# EtherWiz_Sockets.net
KiCad netlist of a schematic drawn in Altium Designer
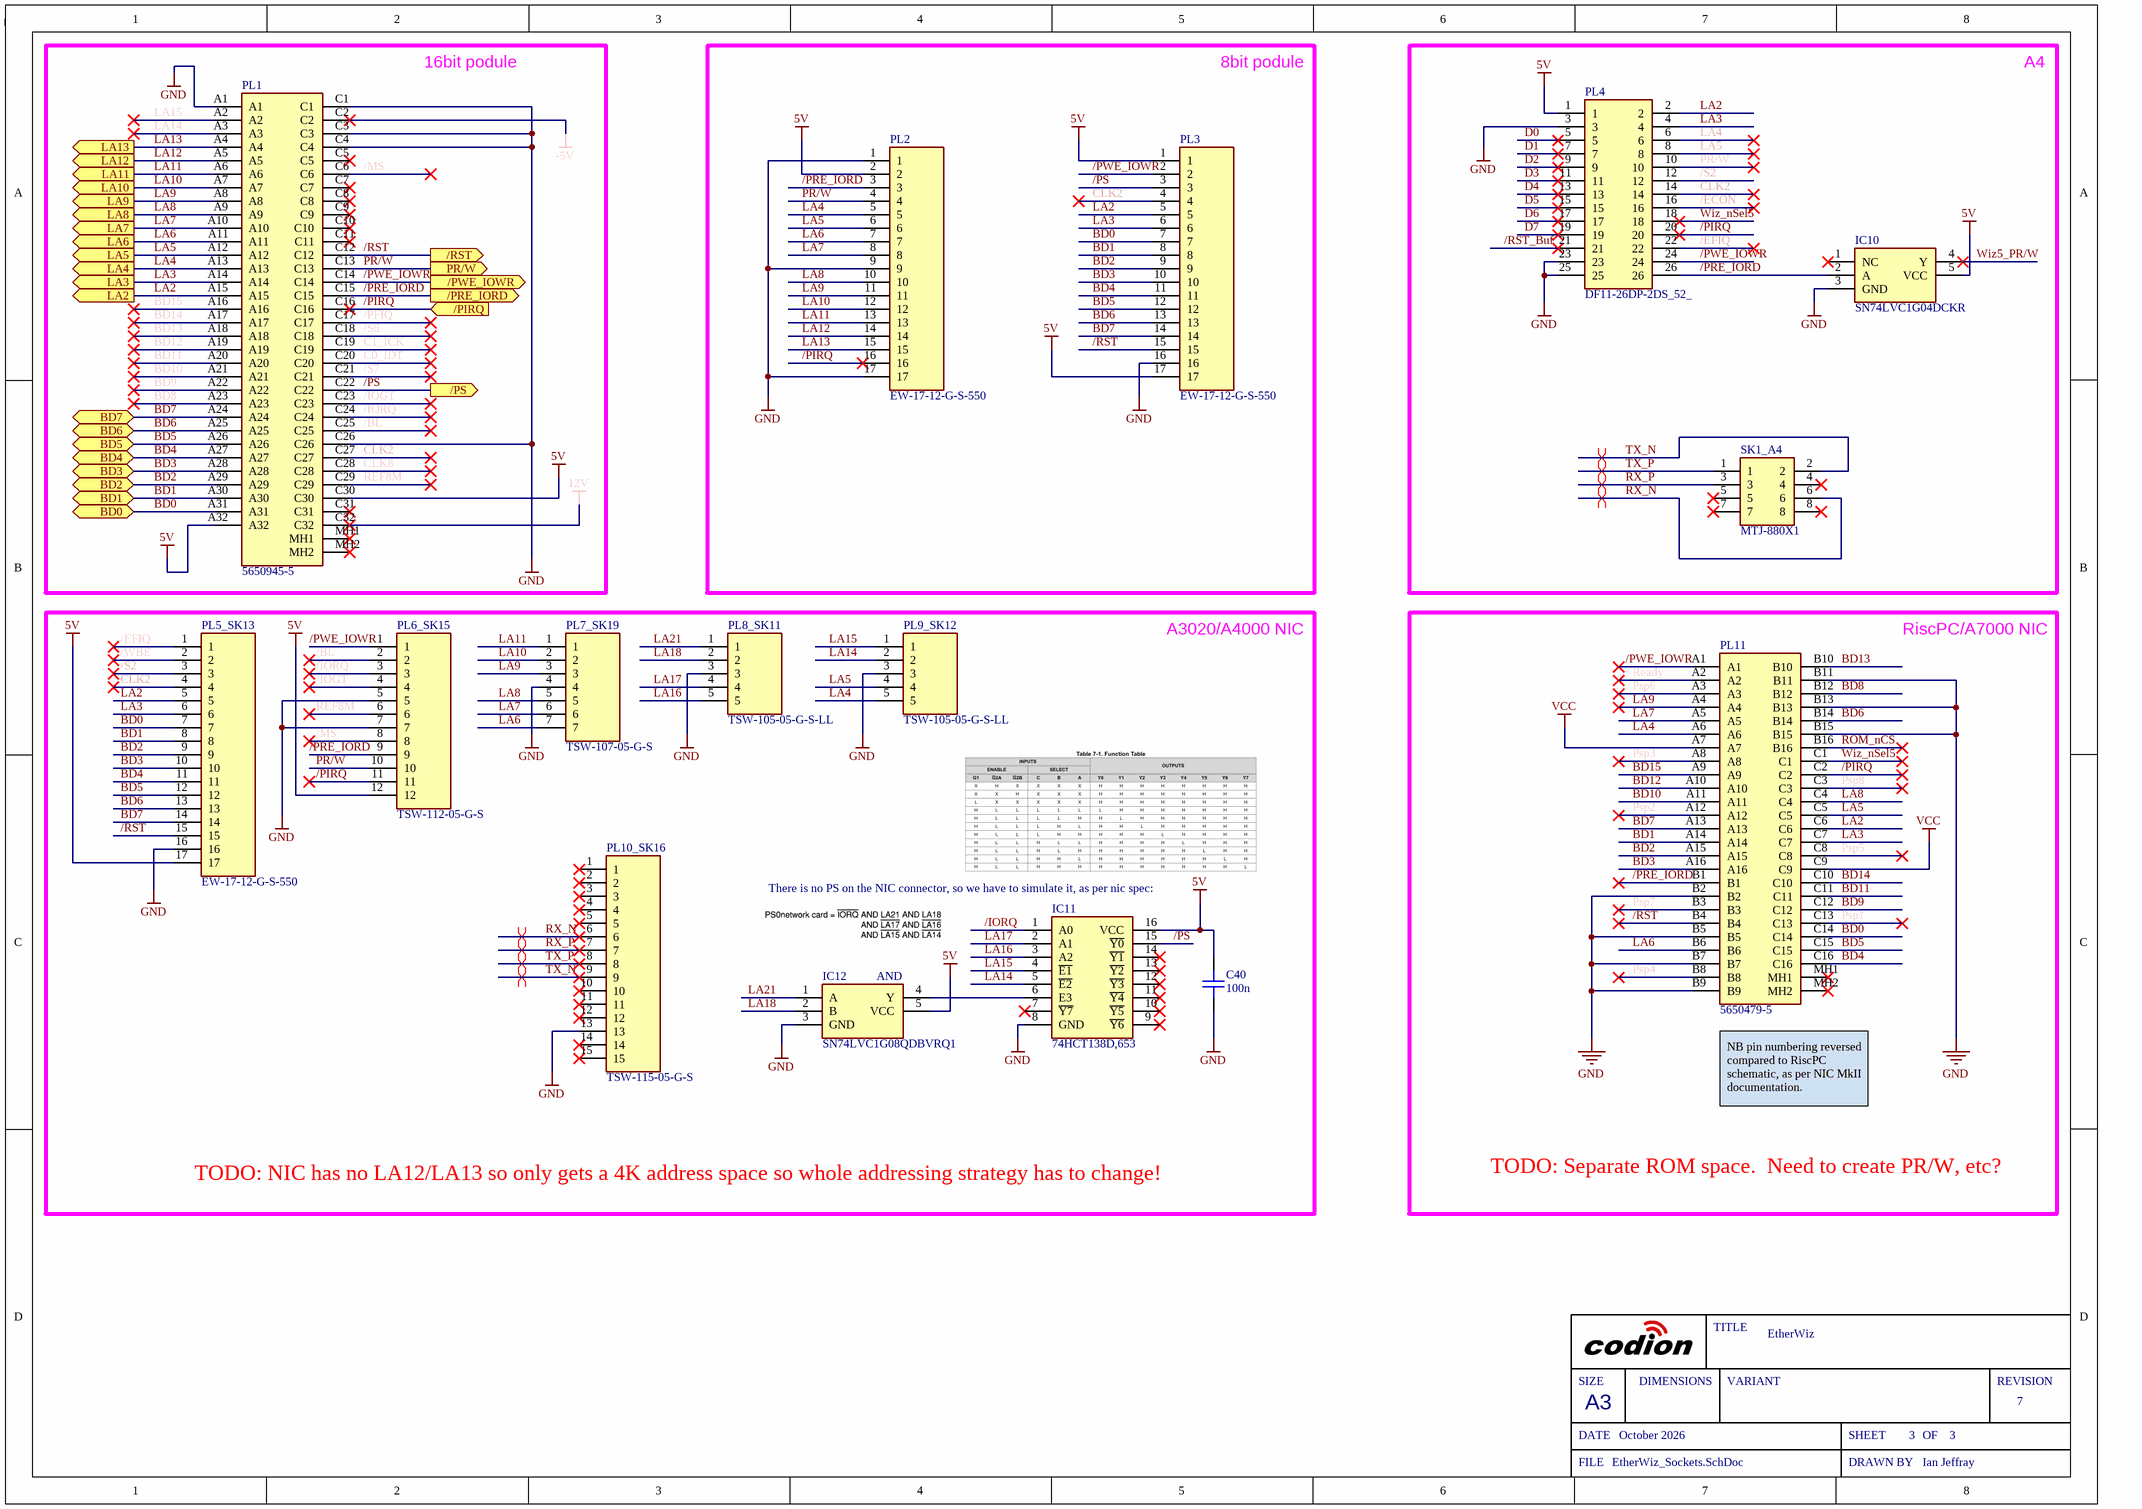
[diagram p0: EtherWiz_Sockets.SchDoc]

(export (version "E")
  (design (tool "Eeschema 10.0.6"))
  (components
    (comp (ref "C40")
      (value "100n")
      (footprint "CAPC1608L")
      (description "CAP 100nF, 0603, 50V, X7R, 10%")
      (fields
        (field (name "DISTRIBUTOR1 PART NO") "CL10B104KB8NNNC")
        (field (name "DISTRIBUTOR2 PART NO") "311-1344-2-ND")
      )
      (libsource (lib "MCP1002_RevC") (part "CAP_100n_0603_50V_0"))
    )
    (comp (ref "IC10")
      (value "SN74LVC1G04DCKR")
      (footprint "SamacSys:SOT65P210X110-5N")
      (description "Integrated Circuit")
      (fields (field (name "MOUSER PART NUMBER") "595-SN74LVC1G04DCKR"))
      (libsource (lib "*") (part "SN74LVC1G04DCKR"))
    )
    (comp (ref "IC11")
      (value "74HCT138D,653")
      (footprint "SamacSys:SOIC127P600X175-16N")
      (description "Integrated Circuit")
      (fields (field (name "MOUSER PART NUMBER") "771-74HCT138D-T"))
      (libsource (lib "*") (part "74HCT138D,653"))
    )
    (comp (ref "IC12")
      (value "SN74LVC1G08QDBVRQ1")
      (footprint "SamacSys:SOT95P280X145-5N")
      (description "Integrated Circuit")
      (fields (field (name "MOUSER PART NUMBER") "595-SN74LVC1G08QDBQ1"))
      (libsource (lib "*") (part "SN74LVC1G08QDBVRQ1"))
    )
    (comp (ref "PL1")
      (value "5650945-5")
      (footprint "SamacSys:56509455")
      (description "Connector")
      (fields (field (name "MOUSER PART NUMBER") "571-5650945-5"))
      (libsource (lib "Acorn") (part "5650945-5"))
    )
    (comp (ref "PL2")
      (value "EW-17-12-G-S-550")
      (footprint "SamacSys:TSW-117-XX-YY-S")
      (description "Connector")
      (fields (field (name "MANUFACTURER_PART_NUMBER") "TSW-117-05-G-S"))
      (libsource (lib "*") (part "TSW-117-05-G-S"))
    )
    (comp (ref "PL3")
      (value "EW-17-12-G-S-550")
      (footprint "SamacSys:TSW-117-XX-YY-S")
      (description "Connector")
      (fields (field (name "MANUFACTURER_PART_NUMBER") "TSW-117-05-G-S"))
      (libsource (lib "*") (part "TSW-117-05-G-S"))
    )
    (comp (ref "PL4")
      (value "DF11-26DP-2DS_52_")
      (footprint "SamacSys:SHDRRA26W50P200_2X13_2800X1000X500P")
      (description "Connector")
      (fields
        (field (name "MANUFACTURER_PART_NUMBER") "DF11-26DP-2DS(52)")
        (field (name "MOUSER PART NUMBER") "798-DF11-26DP-2DS52")
      )
      (libsource (lib "*") (part "DF11-26DP-2DS_52_"))
    )
    (comp (ref "PL5_SK13")
      (value "EW-17-12-G-S-550")
      (footprint "SamacSys:TSW-117-XX-YY-S")
      (description "Connector")
      (fields (field (name "MANUFACTURER_PART_NUMBER") "TSW-117-05-G-S"))
      (libsource (lib "*") (part "TSW-117-05-G-S"))
    )
    (comp (ref "PL6_SK15")
      (value "TSW-112-05-G-S")
      (footprint "SamacSys:TSW-112-XX-YY-S")
      (description "Connector")
      (libsource (lib "*") (part "TSW-112-05-G-S"))
    )
    (comp (ref "PL7_SK19")
      (value "TSW-107-05-G-S")
      (footprint "SamacSys:TSW-107-XX-YY-S")
      (description "Connector")
      (libsource (lib "*") (part "TSW-107-05-G-S"))
    )
    (comp (ref "PL8_SK11")
      (value "TSW-105-05-G-S-LL")
      (footprint "SamacSys:HDRV5W64P0X254_1X5_1270X254X521P")
      (description "Connector")
      (libsource (lib "*") (part "TSW-105-05-G-S-LL"))
    )
    (comp (ref "PL9_SK12")
      (value "TSW-105-05-G-S-LL")
      (footprint "SamacSys:HDRV5W64P0X254_1X5_1270X254X521P")
      (description "Connector")
      (libsource (lib "*") (part "TSW-105-05-G-S-LL"))
    )
    (comp (ref "PL10_SK16")
      (value "TSW-115-05-G-S")
      (footprint "SamacSys:TSW-115-XX-YY-S")
      (description "Connector")
      (libsource (lib "*") (part "TSW-115-05-G-S"))
    )
    (comp (ref "PL11")
      (value "5650479-5")
      (footprint "SamacSys:56504795")
      (description "Connector")
      (fields (field (name "MOUSER PART NUMBER") "571-5650479-5"))
      (libsource (lib "*") (part "5650479-5"))
    )
    (comp (ref "SK1_A4")
      (value "MTJ-880X1")
      (footprint "SamacSys:MTJ880X1")
      (description "Connector")
      (fields (field (name "MOUSER PART NUMBER") "737-MTJ-880X1"))
      (libsource (lib "*") (part "MTJ-880X1"))
    )
  )
  (nets
    (net (code "1") (name "-5V") (class "Default")
      (node (ref "PL1") (pin "C2") (pinfunction "C2_C2") (pintype "passive"))
    )
    (net (code "2") (name "/BD0") (class "Default")
      (node (ref "PL1") (pin "A31") (pinfunction "A31_A31") (pintype "passive"))
      (node (ref "PL11") (pin "C14") (pinfunction "C14_C14") (pintype "passive"))
      (node (ref "PL3") (pin "7") (pinfunction "7_7") (pintype "passive"))
      (node (ref "PL5_SK13") (pin "7") (pinfunction "7_7") (pintype "passive"))
    )
    (net (code "3") (name "/BD1") (class "Default")
      (node (ref "PL1") (pin "A30") (pinfunction "A30_A30") (pintype "passive"))
      (node (ref "PL11") (pin "A14") (pinfunction "A14_A14") (pintype "passive"))
      (node (ref "PL3") (pin "8") (pinfunction "8_8") (pintype "passive"))
      (node (ref "PL5_SK13") (pin "8") (pinfunction "8_8") (pintype "passive"))
    )
    (net (code "4") (name "/BD2") (class "Default")
      (node (ref "PL1") (pin "A29") (pinfunction "A29_A29") (pintype "passive"))
      (node (ref "PL11") (pin "A15") (pinfunction "A15_A15") (pintype "passive"))
      (node (ref "PL3") (pin "9") (pinfunction "9_9") (pintype "passive"))
      (node (ref "PL5_SK13") (pin "9") (pinfunction "9_9") (pintype "passive"))
    )
    (net (code "5") (name "/BD3") (class "Default")
      (node (ref "PL1") (pin "A28") (pinfunction "A28_A28") (pintype "passive"))
      (node (ref "PL11") (pin "A16") (pinfunction "A16_A16") (pintype "passive"))
      (node (ref "PL3") (pin "10") (pinfunction "10_10") (pintype "passive"))
      (node (ref "PL5_SK13") (pin "10") (pinfunction "10_10") (pintype "passive"))
    )
    (net (code "6") (name "/BD4") (class "Default")
      (node (ref "PL1") (pin "A27") (pinfunction "A27_A27") (pintype "passive"))
      (node (ref "PL11") (pin "C16") (pinfunction "C16_C16") (pintype "passive"))
      (node (ref "PL3") (pin "11") (pinfunction "11_11") (pintype "passive"))
      (node (ref "PL5_SK13") (pin "11") (pinfunction "11_11") (pintype "passive"))
    )
    (net (code "7") (name "/BD5") (class "Default")
      (node (ref "PL1") (pin "A26") (pinfunction "A26_A26") (pintype "passive"))
      (node (ref "PL11") (pin "C15") (pinfunction "C15_C15") (pintype "passive"))
      (node (ref "PL3") (pin "12") (pinfunction "12_12") (pintype "passive"))
      (node (ref "PL5_SK13") (pin "12") (pinfunction "12_12") (pintype "passive"))
    )
    (net (code "8") (name "/BD6") (class "Default")
      (node (ref "PL1") (pin "A25") (pinfunction "A25_A25") (pintype "passive"))
      (node (ref "PL11") (pin "B14") (pinfunction "B14_B14") (pintype "passive"))
      (node (ref "PL3") (pin "13") (pinfunction "13_13") (pintype "passive"))
      (node (ref "PL5_SK13") (pin "13") (pinfunction "13_13") (pintype "passive"))
    )
    (net (code "9") (name "/BD7") (class "Default")
      (node (ref "PL1") (pin "A24") (pinfunction "A24_A24") (pintype "passive"))
      (node (ref "PL11") (pin "A13") (pinfunction "A13_A13") (pintype "passive"))
      (node (ref "PL3") (pin "14") (pinfunction "14_14") (pintype "passive"))
      (node (ref "PL5_SK13") (pin "14") (pinfunction "14_14") (pintype "passive"))
    )
    (net (code "10") (name "/BD8") (class "Default")
      (node (ref "PL1") (pin "A23") (pinfunction "A23_A23") (pintype "passive"))
      (node (ref "PL11") (pin "B12") (pinfunction "B12_B12") (pintype "passive"))
    )
    (net (code "11") (name "/BD9") (class "Default")
      (node (ref "PL1") (pin "A22") (pinfunction "A22_A22") (pintype "passive"))
      (node (ref "PL11") (pin "C12") (pinfunction "C12_C12") (pintype "passive"))
    )
    (net (code "12") (name "/BD10") (class "Default")
      (node (ref "PL1") (pin "A21") (pinfunction "A21_A21") (pintype "passive"))
      (node (ref "PL11") (pin "A11") (pinfunction "A11_A11") (pintype "passive"))
    )
    (net (code "13") (name "/BD11") (class "Default")
      (node (ref "PL1") (pin "A20") (pinfunction "A20_A20") (pintype "passive"))
      (node (ref "PL11") (pin "C11") (pinfunction "C11_C11") (pintype "passive"))
    )
    (net (code "14") (name "/BD12") (class "Default")
      (node (ref "PL1") (pin "A19") (pinfunction "A19_A19") (pintype "passive"))
      (node (ref "PL11") (pin "A10") (pinfunction "A10_A10") (pintype "passive"))
    )
    (net (code "15") (name "/BD13") (class "Default")
      (node (ref "PL1") (pin "A18") (pinfunction "A18_A18") (pintype "passive"))
      (node (ref "PL11") (pin "B10") (pinfunction "B10_B10") (pintype "passive"))
    )
    (net (code "16") (name "/BD14") (class "Default")
      (node (ref "PL1") (pin "A17") (pinfunction "A17_A17") (pintype "passive"))
      (node (ref "PL11") (pin "C10") (pinfunction "C10_C10") (pintype "passive"))
    )
    (net (code "17") (name "/BD15") (class "Default")
      (node (ref "PL1") (pin "A16") (pinfunction "A16_A16") (pintype "passive"))
      (node (ref "PL11") (pin "A9") (pinfunction "A9_A9") (pintype "passive"))
    )
    (net (code "18") (name "/C0_IDT") (class "Default")
      (node (ref "PL1") (pin "C20") (pinfunction "C20_C20") (pintype "passive+no_connect"))
    )
    (net (code "19") (name "/C1_ICK") (class "Default")
      (node (ref "PL1") (pin "C19") (pinfunction "C19_C19") (pintype "passive+no_connect"))
    )
    (net (code "20") (name "/CLK2") (class "Default")
      (node (ref "PL1") (pin "C27") (pinfunction "C27_C27") (pintype "passive"))
      (node (ref "PL3") (pin "4") (pinfunction "4_4") (pintype "passive"))
      (node (ref "PL4") (pin "14") (pinfunction "14_14") (pintype "passive"))
      (node (ref "PL5_SK13") (pin "4") (pinfunction "4_4") (pintype "passive"))
    )
    (net (code "21") (name "/CLK8") (class "Default")
      (node (ref "PL1") (pin "C28") (pinfunction "C28_C28") (pintype "passive+no_connect"))
    )
    (net (code "22") (name "/D0") (class "Default")
      (node (ref "PL4") (pin "5") (pinfunction "5_5") (pintype "passive+no_connect"))
    )
    (net (code "23") (name "/D1") (class "Default")
      (node (ref "PL4") (pin "7") (pinfunction "7_7") (pintype "passive+no_connect"))
    )
    (net (code "24") (name "/D2") (class "Default")
      (node (ref "PL4") (pin "9") (pinfunction "9_9") (pintype "passive+no_connect"))
    )
    (net (code "25") (name "/D3") (class "Default")
      (node (ref "PL4") (pin "11") (pinfunction "11_11") (pintype "passive+no_connect"))
    )
    (net (code "26") (name "/D4") (class "Default")
      (node (ref "PL4") (pin "13") (pinfunction "13_13") (pintype "passive+no_connect"))
    )
    (net (code "27") (name "/D5") (class "Default")
      (node (ref "PL4") (pin "15") (pinfunction "15_15") (pintype "passive+no_connect"))
    )
    (net (code "28") (name "/D6") (class "Default")
      (node (ref "PL4") (pin "17") (pinfunction "17_17") (pintype "passive+no_connect"))
    )
    (net (code "29") (name "/D7") (class "Default")
      (node (ref "PL4") (pin "19") (pinfunction "19_19") (pintype "passive+no_connect"))
    )
    (net (code "30") (name "/LA2") (class "Default")
      (node (ref "PL1") (pin "A15") (pinfunction "A15_A15") (pintype "passive"))
      (node (ref "PL11") (pin "C6") (pinfunction "C6_C6") (pintype "passive"))
      (node (ref "PL3") (pin "5") (pinfunction "5_5") (pintype "passive"))
      (node (ref "PL4") (pin "2") (pinfunction "2_2") (pintype "passive"))
      (node (ref "PL5_SK13") (pin "5") (pinfunction "5_5") (pintype "passive"))
    )
    (net (code "31") (name "/LA3") (class "Default")
      (node (ref "PL1") (pin "A14") (pinfunction "A14_A14") (pintype "passive"))
      (node (ref "PL11") (pin "C7") (pinfunction "C7_C7") (pintype "passive"))
      (node (ref "PL3") (pin "6") (pinfunction "6_6") (pintype "passive"))
      (node (ref "PL4") (pin "4") (pinfunction "4_4") (pintype "passive"))
      (node (ref "PL5_SK13") (pin "6") (pinfunction "6_6") (pintype "passive"))
    )
    (net (code "32") (name "/LA4") (class "Default")
      (node (ref "PL1") (pin "A13") (pinfunction "A13_A13") (pintype "passive"))
      (node (ref "PL11") (pin "A6") (pinfunction "A6_A6") (pintype "passive"))
      (node (ref "PL2") (pin "5") (pinfunction "5_5") (pintype "passive"))
      (node (ref "PL4") (pin "6") (pinfunction "6_6") (pintype "passive"))
      (node (ref "PL9_SK12") (pin "5") (pinfunction "5_5") (pintype "passive"))
    )
    (net (code "33") (name "/LA5") (class "Default")
      (node (ref "PL1") (pin "A12") (pinfunction "A12_A12") (pintype "passive"))
      (node (ref "PL11") (pin "C5") (pinfunction "C5_C5") (pintype "passive"))
      (node (ref "PL2") (pin "6") (pinfunction "6_6") (pintype "passive"))
      (node (ref "PL4") (pin "8") (pinfunction "8_8") (pintype "passive"))
      (node (ref "PL9_SK12") (pin "4") (pinfunction "4_4") (pintype "passive"))
    )
    (net (code "34") (name "/LA6") (class "Default")
      (node (ref "PL1") (pin "A11") (pinfunction "A11_A11") (pintype "passive"))
      (node (ref "PL11") (pin "B6") (pinfunction "B6_B6") (pintype "passive"))
      (node (ref "PL2") (pin "7") (pinfunction "7_7") (pintype "passive"))
      (node (ref "PL7_SK19") (pin "7") (pinfunction "7_7") (pintype "passive"))
    )
    (net (code "35") (name "/LA7") (class "Default")
      (node (ref "PL1") (pin "A10") (pinfunction "A10_A10") (pintype "passive"))
      (node (ref "PL11") (pin "A5") (pinfunction "A5_A5") (pintype "passive"))
      (node (ref "PL2") (pin "8") (pinfunction "8_8") (pintype "passive"))
      (node (ref "PL7_SK19") (pin "6") (pinfunction "6_6") (pintype "passive"))
    )
    (net (code "36") (name "/LA8") (class "Default")
      (node (ref "PL1") (pin "A9") (pinfunction "A9_A9") (pintype "passive"))
      (node (ref "PL11") (pin "C4") (pinfunction "C4_C4") (pintype "passive"))
      (node (ref "PL2") (pin "10") (pinfunction "10_10") (pintype "passive"))
      (node (ref "PL7_SK19") (pin "5") (pinfunction "5_5") (pintype "passive"))
    )
    (net (code "37") (name "/LA9") (class "Default")
      (node (ref "PL1") (pin "A8") (pinfunction "A8_A8") (pintype "passive"))
      (node (ref "PL11") (pin "A4") (pinfunction "A4_A4") (pintype "passive"))
      (node (ref "PL2") (pin "11") (pinfunction "11_11") (pintype "passive"))
      (node (ref "PL7_SK19") (pin "3") (pinfunction "3_3") (pintype "passive"))
    )
    (net (code "38") (name "/LA10") (class "Default")
      (node (ref "PL1") (pin "A7") (pinfunction "A7_A7") (pintype "passive"))
      (node (ref "PL2") (pin "12") (pinfunction "12_12") (pintype "passive"))
      (node (ref "PL7_SK19") (pin "2") (pinfunction "2_2") (pintype "passive"))
    )
    (net (code "39") (name "/LA11") (class "Default")
      (node (ref "PL1") (pin "A6") (pinfunction "A6_A6") (pintype "passive"))
      (node (ref "PL2") (pin "13") (pinfunction "13_13") (pintype "passive"))
      (node (ref "PL7_SK19") (pin "1") (pinfunction "1_1") (pintype "passive"))
    )
    (net (code "40") (name "/LA12") (class "Default")
      (node (ref "PL1") (pin "A5") (pinfunction "A5_A5") (pintype "passive"))
      (node (ref "PL2") (pin "14") (pinfunction "14_14") (pintype "passive"))
    )
    (net (code "41") (name "/LA13") (class "Default")
      (node (ref "PL1") (pin "A4") (pinfunction "A4_A4") (pintype "passive"))
      (node (ref "PL2") (pin "15") (pinfunction "15_15") (pintype "passive"))
    )
    (net (code "42") (name "/LA14") (class "Default")
      (node (ref "IC11") (pin "5") (pinfunction "~{E2}_5") (pintype "passive"))
      (node (ref "PL1") (pin "A3") (pinfunction "A3_A3") (pintype "passive"))
      (node (ref "PL9_SK12") (pin "2") (pinfunction "2_2") (pintype "passive"))
    )
    (net (code "43") (name "/LA15") (class "Default")
      (node (ref "IC11") (pin "4") (pinfunction "~{E1}_4") (pintype "passive"))
      (node (ref "PL1") (pin "A2") (pinfunction "A2_A2") (pintype "passive"))
      (node (ref "PL9_SK12") (pin "1") (pinfunction "1_1") (pintype "passive"))
    )
    (net (code "44") (name "/LA16") (class "Default")
      (node (ref "IC11") (pin "3") (pinfunction "A2_3") (pintype "passive"))
      (node (ref "PL8_SK11") (pin "5") (pinfunction "5_5") (pintype "passive"))
    )
    (net (code "45") (name "/LA17") (class "Default")
      (node (ref "IC11") (pin "2") (pinfunction "A1_2") (pintype "passive"))
      (node (ref "PL8_SK11") (pin "4") (pinfunction "4_4") (pintype "passive"))
    )
    (net (code "46") (name "/LA18") (class "Default")
      (node (ref "IC12") (pin "2") (pinfunction "B_2") (pintype "passive"))
      (node (ref "PL8_SK11") (pin "2") (pinfunction "2_2") (pintype "passive"))
    )
    (net (code "47") (name "/LA21") (class "Default")
      (node (ref "IC12") (pin "1") (pinfunction "A_1") (pintype "passive"))
      (node (ref "PL8_SK11") (pin "1") (pinfunction "1_1") (pintype "passive"))
    )
    (net (code "48") (name "/PR{slash}W") (class "Default")
      (node (ref "PL1") (pin "C13") (pinfunction "C13_C13") (pintype "passive"))
      (node (ref "PL2") (pin "4") (pinfunction "4_4") (pintype "passive"))
      (node (ref "PL4") (pin "10") (pinfunction "10_10") (pintype "passive"))
      (node (ref "PL6_SK15") (pin "10") (pinfunction "10_10") (pintype "passive"))
    )
    (net (code "49") (name "/Psp1") (class "Default")
      (node (ref "PL11") (pin "C13") (pinfunction "C13_C13") (pintype "passive+no_connect"))
    )
    (net (code "50") (name "/Psp2") (class "Default")
      (node (ref "PL11") (pin "A12") (pinfunction "A12_A12") (pintype "passive+no_connect"))
    )
    (net (code "51") (name "/Psp3") (class "Default")
      (node (ref "PL11") (pin "A8") (pinfunction "A8_A8") (pintype "passive+no_connect"))
    )
    (net (code "52") (name "/Psp4") (class "Default")
      (node (ref "PL11") (pin "B8") (pinfunction "B8_B8") (pintype "passive+no_connect"))
    )
    (net (code "53") (name "/Psp5") (class "Default")
      (node (ref "PL11") (pin "C8") (pinfunction "C8_C8") (pintype "passive+no_connect"))
    )
    (net (code "54") (name "/Psp6") (class "Default")
      (node (ref "PL11") (pin "A3") (pinfunction "A3_A3") (pintype "passive+no_connect"))
    )
    (net (code "55") (name "/Psp7") (class "Default")
      (node (ref "PL11") (pin "B3") (pinfunction "B3_B3") (pintype "passive+no_connect"))
    )
    (net (code "56") (name "/Psp8") (class "Default")
      (node (ref "PL11") (pin "C3") (pinfunction "C3_C3") (pintype "passive+no_connect"))
    )
    (net (code "57") (name "/REF8M") (class "Default")
      (node (ref "PL1") (pin "C29") (pinfunction "C29_C29") (pintype "passive"))
      (node (ref "PL6_SK15") (pin "6") (pinfunction "6_6") (pintype "passive"))
    )
    (net (code "58") (name "/ROM_nCS") (class "Default")
      (node (ref "PL11") (pin "B16") (pinfunction "B16_B16") (pintype "passive+no_connect"))
    )
    (net (code "59") (name "/RX_N") (class "Default")
      (node (ref "PL10_SK16") (pin "6") (pinfunction "6_6") (pintype "passive"))
      (node (ref "SK1_A4") (pin "6") (pinfunction "6_6") (pintype "passive"))
    )
    (net (code "60") (name "/RX_P") (class "Default")
      (node (ref "PL10_SK16") (pin "7") (pinfunction "7_7") (pintype "passive"))
      (node (ref "SK1_A4") (pin "3") (pinfunction "3_3") (pintype "passive"))
    )
    (net (code "61") (name "/Ready") (class "Default")
      (node (ref "PL11") (pin "A2") (pinfunction "A2_A2") (pintype "passive+no_connect"))
    )
    (net (code "62") (name "/TX_N") (class "Default")
      (node (ref "PL10_SK16") (pin "9") (pinfunction "9_9") (pintype "passive"))
      (node (ref "SK1_A4") (pin "2") (pinfunction "2_2") (pintype "passive"))
    )
    (net (code "63") (name "/TX_P") (class "Default")
      (node (ref "PL10_SK16") (pin "8") (pinfunction "8_8") (pintype "passive"))
      (node (ref "SK1_A4") (pin "1") (pinfunction "1_1") (pintype "passive"))
    )
    (net (code "64") (name "/Wiz5_PR{slash}W") (class "Default")
      (node (ref "IC10") (pin "4") (pinfunction "Y_4") (pintype "passive+no_connect"))
    )
    (net (code "65") (name "/Wiz_nSel5") (class "Default")
      (node (ref "PL11") (pin "C1") (pinfunction "C1_C1") (pintype "passive"))
      (node (ref "PL4") (pin "18") (pinfunction "18_18") (pintype "passive"))
    )
    (net (code "66") (name "/{slash}BL") (class "Default")
      (node (ref "PL1") (pin "C25") (pinfunction "C25_C25") (pintype "passive"))
      (node (ref "PL6_SK15") (pin "2") (pinfunction "2_2") (pintype "passive"))
    )
    (net (code "67") (name "/{slash}ECON") (class "Default")
      (node (ref "PL4") (pin "16") (pinfunction "16_16") (pintype "passive+no_connect"))
    )
    (net (code "68") (name "/{slash}EFIQ") (class "Default")
      (node (ref "PL4") (pin "22") (pinfunction "22_22") (pintype "passive"))
      (node (ref "PL5_SK13") (pin "1") (pinfunction "1_1") (pintype "passive"))
    )
    (net (code "69") (name "/{slash}IOGT") (class "Default")
      (node (ref "PL1") (pin "C23") (pinfunction "C23_C23") (pintype "passive"))
      (node (ref "PL6_SK15") (pin "4") (pinfunction "4_4") (pintype "passive"))
    )
    (net (code "70") (name "/{slash}IORQ") (class "Default")
      (node (ref "IC11") (pin "1") (pinfunction "A0_1") (pintype "passive"))
      (node (ref "PL1") (pin "C24") (pinfunction "C24_C24") (pintype "passive"))
      (node (ref "PL6_SK15") (pin "3") (pinfunction "3_3") (pintype "passive"))
    )
    (net (code "71") (name "/{slash}MS") (class "Default")
      (node (ref "PL1") (pin "C6") (pinfunction "C6_C6") (pintype "passive"))
      (node (ref "PL6_SK15") (pin "8") (pinfunction "8_8") (pintype "passive"))
    )
    (net (code "72") (name "/{slash}PFIQ") (class "Default")
      (node (ref "PL1") (pin "C17") (pinfunction "C17_C17") (pintype "passive+no_connect"))
    )
    (net (code "73") (name "/{slash}PIRQ") (class "Default")
      (node (ref "PL1") (pin "C16") (pinfunction "C16_C16") (pintype "passive"))
      (node (ref "PL11") (pin "C2") (pinfunction "C2_C2") (pintype "passive"))
      (node (ref "PL2") (pin "16") (pinfunction "16_16") (pintype "passive"))
      (node (ref "PL4") (pin "20") (pinfunction "20_20") (pintype "passive"))
      (node (ref "PL6_SK15") (pin "11") (pinfunction "11_11") (pintype "passive"))
    )
    (net (code "74") (name "/{slash}PRE_IORD") (class "Default")
      (node (ref "IC10") (pin "2") (pinfunction "A_2") (pintype "passive"))
      (node (ref "PL1") (pin "C15") (pinfunction "C15_C15") (pintype "passive"))
      (node (ref "PL11") (pin "B1") (pinfunction "B1_B1") (pintype "passive"))
      (node (ref "PL2") (pin "3") (pinfunction "3_3") (pintype "passive"))
      (node (ref "PL4") (pin "26") (pinfunction "26_26") (pintype "passive"))
      (node (ref "PL6_SK15") (pin "9") (pinfunction "9_9") (pintype "passive"))
    )
    (net (code "75") (name "/{slash}PS") (class "Default")
      (node (ref "IC11") (pin "15") (pinfunction "~{Y0}_15") (pintype "passive"))
      (node (ref "PL1") (pin "C22") (pinfunction "C22_C22") (pintype "passive"))
      (node (ref "PL3") (pin "3") (pinfunction "3_3") (pintype "passive"))
    )
    (net (code "76") (name "/{slash}PWE_IOWR") (class "Default")
      (node (ref "PL1") (pin "C14") (pinfunction "C14_C14") (pintype "passive"))
      (node (ref "PL11") (pin "A1") (pinfunction "A1_A1") (pintype "passive"))
      (node (ref "PL3") (pin "2") (pinfunction "2_2") (pintype "passive"))
      (node (ref "PL4") (pin "24") (pinfunction "24_24") (pintype "passive"))
      (node (ref "PL6_SK15") (pin "1") (pinfunction "1_1") (pintype "passive"))
    )
    (net (code "77") (name "/{slash}RST") (class "Default")
      (node (ref "PL1") (pin "C12") (pinfunction "C12_C12") (pintype "passive"))
      (node (ref "PL11") (pin "B4") (pinfunction "B4_B4") (pintype "passive"))
      (node (ref "PL3") (pin "15") (pinfunction "15_15") (pintype "passive"))
      (node (ref "PL5_SK13") (pin "15") (pinfunction "15_15") (pintype "passive"))
    )
    (net (code "78") (name "/{slash}RST_Buf") (class "Default")
      (node (ref "PL4") (pin "21") (pinfunction "21_21") (pintype "passive+no_connect"))
    )
    (net (code "79") (name "/{slash}S2") (class "Default")
      (node (ref "PL4") (pin "12") (pinfunction "12_12") (pintype "passive"))
      (node (ref "PL5_SK13") (pin "3") (pinfunction "3_3") (pintype "passive"))
    )
    (net (code "80") (name "/{slash}S6") (class "Default")
      (node (ref "PL1") (pin "C18") (pinfunction "C18_C18") (pintype "passive+no_connect"))
    )
    (net (code "81") (name "/{slash}S7") (class "Default")
      (node (ref "PL1") (pin "C21") (pinfunction "C21_C21") (pintype "passive+no_connect"))
    )
    (net (code "82") (name "/{slash}WBE") (class "Default")
      (node (ref "PL5_SK13") (pin "2") (pinfunction "2_2") (pintype "passive+no_connect"))
    )
    (net (code "83") (name "5V") (class "Default")
      (node (ref "C40") (pin "2") (pintype "passive"))
      (node (ref "IC10") (pin "5") (pinfunction "VCC_5") (pintype "passive"))
      (node (ref "IC11") (pin "16") (pinfunction "VCC_16") (pintype "passive"))
      (node (ref "IC12") (pin "5") (pinfunction "VCC_5") (pintype "power_in"))
      (node (ref "PL1") (pin "A32") (pinfunction "A32_A32") (pintype "passive"))
      (node (ref "PL1") (pin "C30") (pinfunction "C30_C30") (pintype "passive"))
      (node (ref "PL2") (pin "2") (pinfunction "2_2") (pintype "passive"))
      (node (ref "PL3") (pin "1") (pinfunction "1_1") (pintype "passive"))
      (node (ref "PL3") (pin "17") (pinfunction "17_17") (pintype "passive"))
      (node (ref "PL4") (pin "1") (pinfunction "1_1") (pintype "passive"))
      (node (ref "PL5_SK13") (pin "17") (pinfunction "17_17") (pintype "passive"))
      (node (ref "PL6_SK15") (pin "12") (pinfunction "12_12") (pintype "passive"))
    )
    (net (code "84") (name "12V") (class "Default")
      (node (ref "PL1") (pin "C32") (pinfunction "C32_C32") (pintype "passive"))
    )
    (net (code "85") (name "GND") (class "Default")
      (node (ref "C40") (pin "1") (pintype "passive"))
      (node (ref "IC10") (pin "3") (pinfunction "GND_3") (pintype "passive"))
      (node (ref "IC11") (pin "8") (pinfunction "GND_8") (pintype "passive"))
      (node (ref "IC12") (pin "3") (pinfunction "GND_3") (pintype "power_in"))
      (node (ref "PL1") (pin "A1") (pinfunction "A1_A1") (pintype "passive"))
      (node (ref "PL1") (pin "C1") (pinfunction "C1_C1") (pintype "passive"))
      (node (ref "PL1") (pin "C26") (pinfunction "C26_C26") (pintype "passive"))
      (node (ref "PL1") (pin "C3") (pinfunction "C3_C3") (pintype "passive"))
      (node (ref "PL1") (pin "C4") (pinfunction "C4_C4") (pintype "passive"))
      (node (ref "PL10_SK16") (pin "13") (pinfunction "13_13") (pintype "passive"))
      (node (ref "PL11") (pin "B11") (pinfunction "B11_B11") (pintype "passive"))
      (node (ref "PL11") (pin "B13") (pinfunction "B13_B13") (pintype "passive"))
      (node (ref "PL11") (pin "B15") (pinfunction "B15_B15") (pintype "passive"))
      (node (ref "PL11") (pin "B2") (pinfunction "B2_B2") (pintype "passive"))
      (node (ref "PL11") (pin "B5") (pinfunction "B5_B5") (pintype "passive"))
      (node (ref "PL11") (pin "B7") (pinfunction "B7_B7") (pintype "passive"))
      (node (ref "PL11") (pin "B9") (pinfunction "B9_B9") (pintype "passive"))
      (node (ref "PL2") (pin "1") (pinfunction "1_1") (pintype "passive"))
      (node (ref "PL2") (pin "17") (pinfunction "17_17") (pintype "passive"))
      (node (ref "PL2") (pin "9") (pinfunction "9_9") (pintype "passive"))
      (node (ref "PL3") (pin "16") (pinfunction "16_16") (pintype "passive"))
      (node (ref "PL4") (pin "23") (pinfunction "23_23") (pintype "passive"))
      (node (ref "PL4") (pin "25") (pinfunction "25_25") (pintype "passive"))
      (node (ref "PL4") (pin "3") (pinfunction "3_3") (pintype "passive"))
      (node (ref "PL5_SK13") (pin "16") (pinfunction "16_16") (pintype "passive"))
      (node (ref "PL6_SK15") (pin "5") (pinfunction "5_5") (pintype "passive"))
      (node (ref "PL6_SK15") (pin "7") (pinfunction "7_7") (pintype "passive"))
      (node (ref "PL7_SK19") (pin "4") (pinfunction "4_4") (pintype "passive"))
      (node (ref "PL8_SK11") (pin "3") (pinfunction "3_3") (pintype "passive"))
      (node (ref "PL9_SK12") (pin "3") (pinfunction "3_3") (pintype "passive"))
    )
    (net (code "86") (name "Net-(IC11-E3)") (class "Default")
      (node (ref "IC11") (pin "6") (pinfunction "E3_6") (pintype "passive"))
      (node (ref "IC12") (pin "4") (pinfunction "Y_4") (pintype "passive"))
    )
    (net (code "87") (name "VCC") (class "Default")
      (node (ref "PL11") (pin "A7") (pinfunction "A7_A7") (pintype "passive"))
      (node (ref "PL11") (pin "C9") (pinfunction "C9_C9") (pintype "passive"))
    )
    (net (code "88") (name "unconnected-(IC10-NC-Pad1)") (class "Default")
      (node (ref "IC10") (pin "1") (pinfunction "NC_1") (pintype "passive+no_connect"))
    )
    (net (code "89") (name "unconnected-(IC11-~{Y1}-Pad14)") (class "Default")
      (node (ref "IC11") (pin "14") (pinfunction "~{Y1}_14") (pintype "passive+no_connect"))
    )
    (net (code "90") (name "unconnected-(IC11-~{Y2}-Pad13)") (class "Default")
      (node (ref "IC11") (pin "13") (pinfunction "~{Y2}_13") (pintype "passive+no_connect"))
    )
    (net (code "91") (name "unconnected-(IC11-~{Y3}-Pad12)") (class "Default")
      (node (ref "IC11") (pin "12") (pinfunction "~{Y3}_12") (pintype "passive+no_connect"))
    )
    (net (code "92") (name "unconnected-(IC11-~{Y4}-Pad11)") (class "Default")
      (node (ref "IC11") (pin "11") (pinfunction "~{Y4}_11") (pintype "passive+no_connect"))
    )
    (net (code "93") (name "unconnected-(IC11-~{Y5}-Pad10)") (class "Default")
      (node (ref "IC11") (pin "10") (pinfunction "~{Y5}_10") (pintype "passive+no_connect"))
    )
    (net (code "94") (name "unconnected-(IC11-~{Y6}-Pad9)") (class "Default")
      (node (ref "IC11") (pin "9") (pinfunction "~{Y6}_9") (pintype "passive+no_connect"))
    )
    (net (code "95") (name "unconnected-(IC11-~{Y7}-Pad7)") (class "Default")
      (node (ref "IC11") (pin "7") (pinfunction "~{Y7}_7") (pintype "passive+no_connect"))
    )
    (net (code "96") (name "unconnected-(PL1-PadC5)") (class "Default")
      (node (ref "PL1") (pin "C5") (pinfunction "C5_C5") (pintype "passive+no_connect"))
    )
    (net (code "97") (name "unconnected-(PL1-PadC7)") (class "Default")
      (node (ref "PL1") (pin "C7") (pinfunction "C7_C7") (pintype "passive+no_connect"))
    )
    (net (code "98") (name "unconnected-(PL1-PadC8)") (class "Default")
      (node (ref "PL1") (pin "C8") (pinfunction "C8_C8") (pintype "passive+no_connect"))
    )
    (net (code "99") (name "unconnected-(PL1-PadC9)") (class "Default")
      (node (ref "PL1") (pin "C9") (pinfunction "C9_C9") (pintype "passive+no_connect"))
    )
    (net (code "100") (name "unconnected-(PL1-PadC10)") (class "Default")
      (node (ref "PL1") (pin "C10") (pinfunction "C10_C10") (pintype "passive+no_connect"))
    )
    (net (code "101") (name "unconnected-(PL1-PadC11)") (class "Default")
      (node (ref "PL1") (pin "C11") (pinfunction "C11_C11") (pintype "passive+no_connect"))
    )
    (net (code "102") (name "unconnected-(PL1-PadC31)") (class "Default")
      (node (ref "PL1") (pin "C31") (pinfunction "C31_C31") (pintype "passive+no_connect"))
    )
    (net (code "103") (name "unconnected-(PL1-PadMH1)") (class "Default")
      (node (ref "PL1") (pin "MH1") (pinfunction "MH1_MH1") (pintype "passive+no_connect"))
    )
    (net (code "104") (name "unconnected-(PL1-PadMH2)") (class "Default")
      (node (ref "PL1") (pin "MH2") (pinfunction "MH2_MH2") (pintype "passive+no_connect"))
    )
    (net (code "105") (name "unconnected-(PL10_SK16-Pad1)") (class "Default")
      (node (ref "PL10_SK16") (pin "1") (pinfunction "1_1") (pintype "passive+no_connect"))
    )
    (net (code "106") (name "unconnected-(PL10_SK16-Pad2)") (class "Default")
      (node (ref "PL10_SK16") (pin "2") (pinfunction "2_2") (pintype "passive+no_connect"))
    )
    (net (code "107") (name "unconnected-(PL10_SK16-Pad3)") (class "Default")
      (node (ref "PL10_SK16") (pin "3") (pinfunction "3_3") (pintype "passive+no_connect"))
    )
    (net (code "108") (name "unconnected-(PL10_SK16-Pad4)") (class "Default")
      (node (ref "PL10_SK16") (pin "4") (pinfunction "4_4") (pintype "passive+no_connect"))
    )
    (net (code "109") (name "unconnected-(PL10_SK16-Pad5)") (class "Default")
      (node (ref "PL10_SK16") (pin "5") (pinfunction "5_5") (pintype "passive+no_connect"))
    )
    (net (code "110") (name "unconnected-(PL10_SK16-Pad10)") (class "Default")
      (node (ref "PL10_SK16") (pin "10") (pinfunction "10_10") (pintype "passive+no_connect"))
    )
    (net (code "111") (name "unconnected-(PL10_SK16-Pad11)") (class "Default")
      (node (ref "PL10_SK16") (pin "11") (pinfunction "11_11") (pintype "passive+no_connect"))
    )
    (net (code "112") (name "unconnected-(PL10_SK16-Pad12)") (class "Default")
      (node (ref "PL10_SK16") (pin "12") (pinfunction "12_12") (pintype "passive+no_connect"))
    )
    (net (code "113") (name "unconnected-(PL10_SK16-Pad14)") (class "Default")
      (node (ref "PL10_SK16") (pin "14") (pinfunction "14_14") (pintype "passive+no_connect"))
    )
    (net (code "114") (name "unconnected-(PL10_SK16-Pad15)") (class "Default")
      (node (ref "PL10_SK16") (pin "15") (pinfunction "15_15") (pintype "passive+no_connect"))
    )
    (net (code "115") (name "unconnected-(PL11-PadMH1)") (class "Default")
      (node (ref "PL11") (pin "MH1") (pinfunction "MH1_MH1") (pintype "passive+no_connect"))
    )
    (net (code "116") (name "unconnected-(PL11-PadMH2)") (class "Default")
      (node (ref "PL11") (pin "MH2") (pinfunction "MH2_MH2") (pintype "passive+no_connect"))
    )
    (net (code "117") (name "unconnected-(SK1_A4-Pad4)") (class "Default")
      (node (ref "SK1_A4") (pin "4") (pinfunction "4_4") (pintype "passive+no_connect"))
    )
    (net (code "118") (name "unconnected-(SK1_A4-Pad5)") (class "Default")
      (node (ref "SK1_A4") (pin "5") (pinfunction "5_5") (pintype "passive+no_connect"))
    )
    (net (code "119") (name "unconnected-(SK1_A4-Pad7)") (class "Default")
      (node (ref "SK1_A4") (pin "7") (pinfunction "7_7") (pintype "passive+no_connect"))
    )
    (net (code "120") (name "unconnected-(SK1_A4-Pad8)") (class "Default")
      (node (ref "SK1_A4") (pin "8") (pinfunction "8_8") (pintype "passive+no_connect"))
    )
  )
)
